# RGBoard.net
KiCad netlist of a schematic drawn in EAGLE
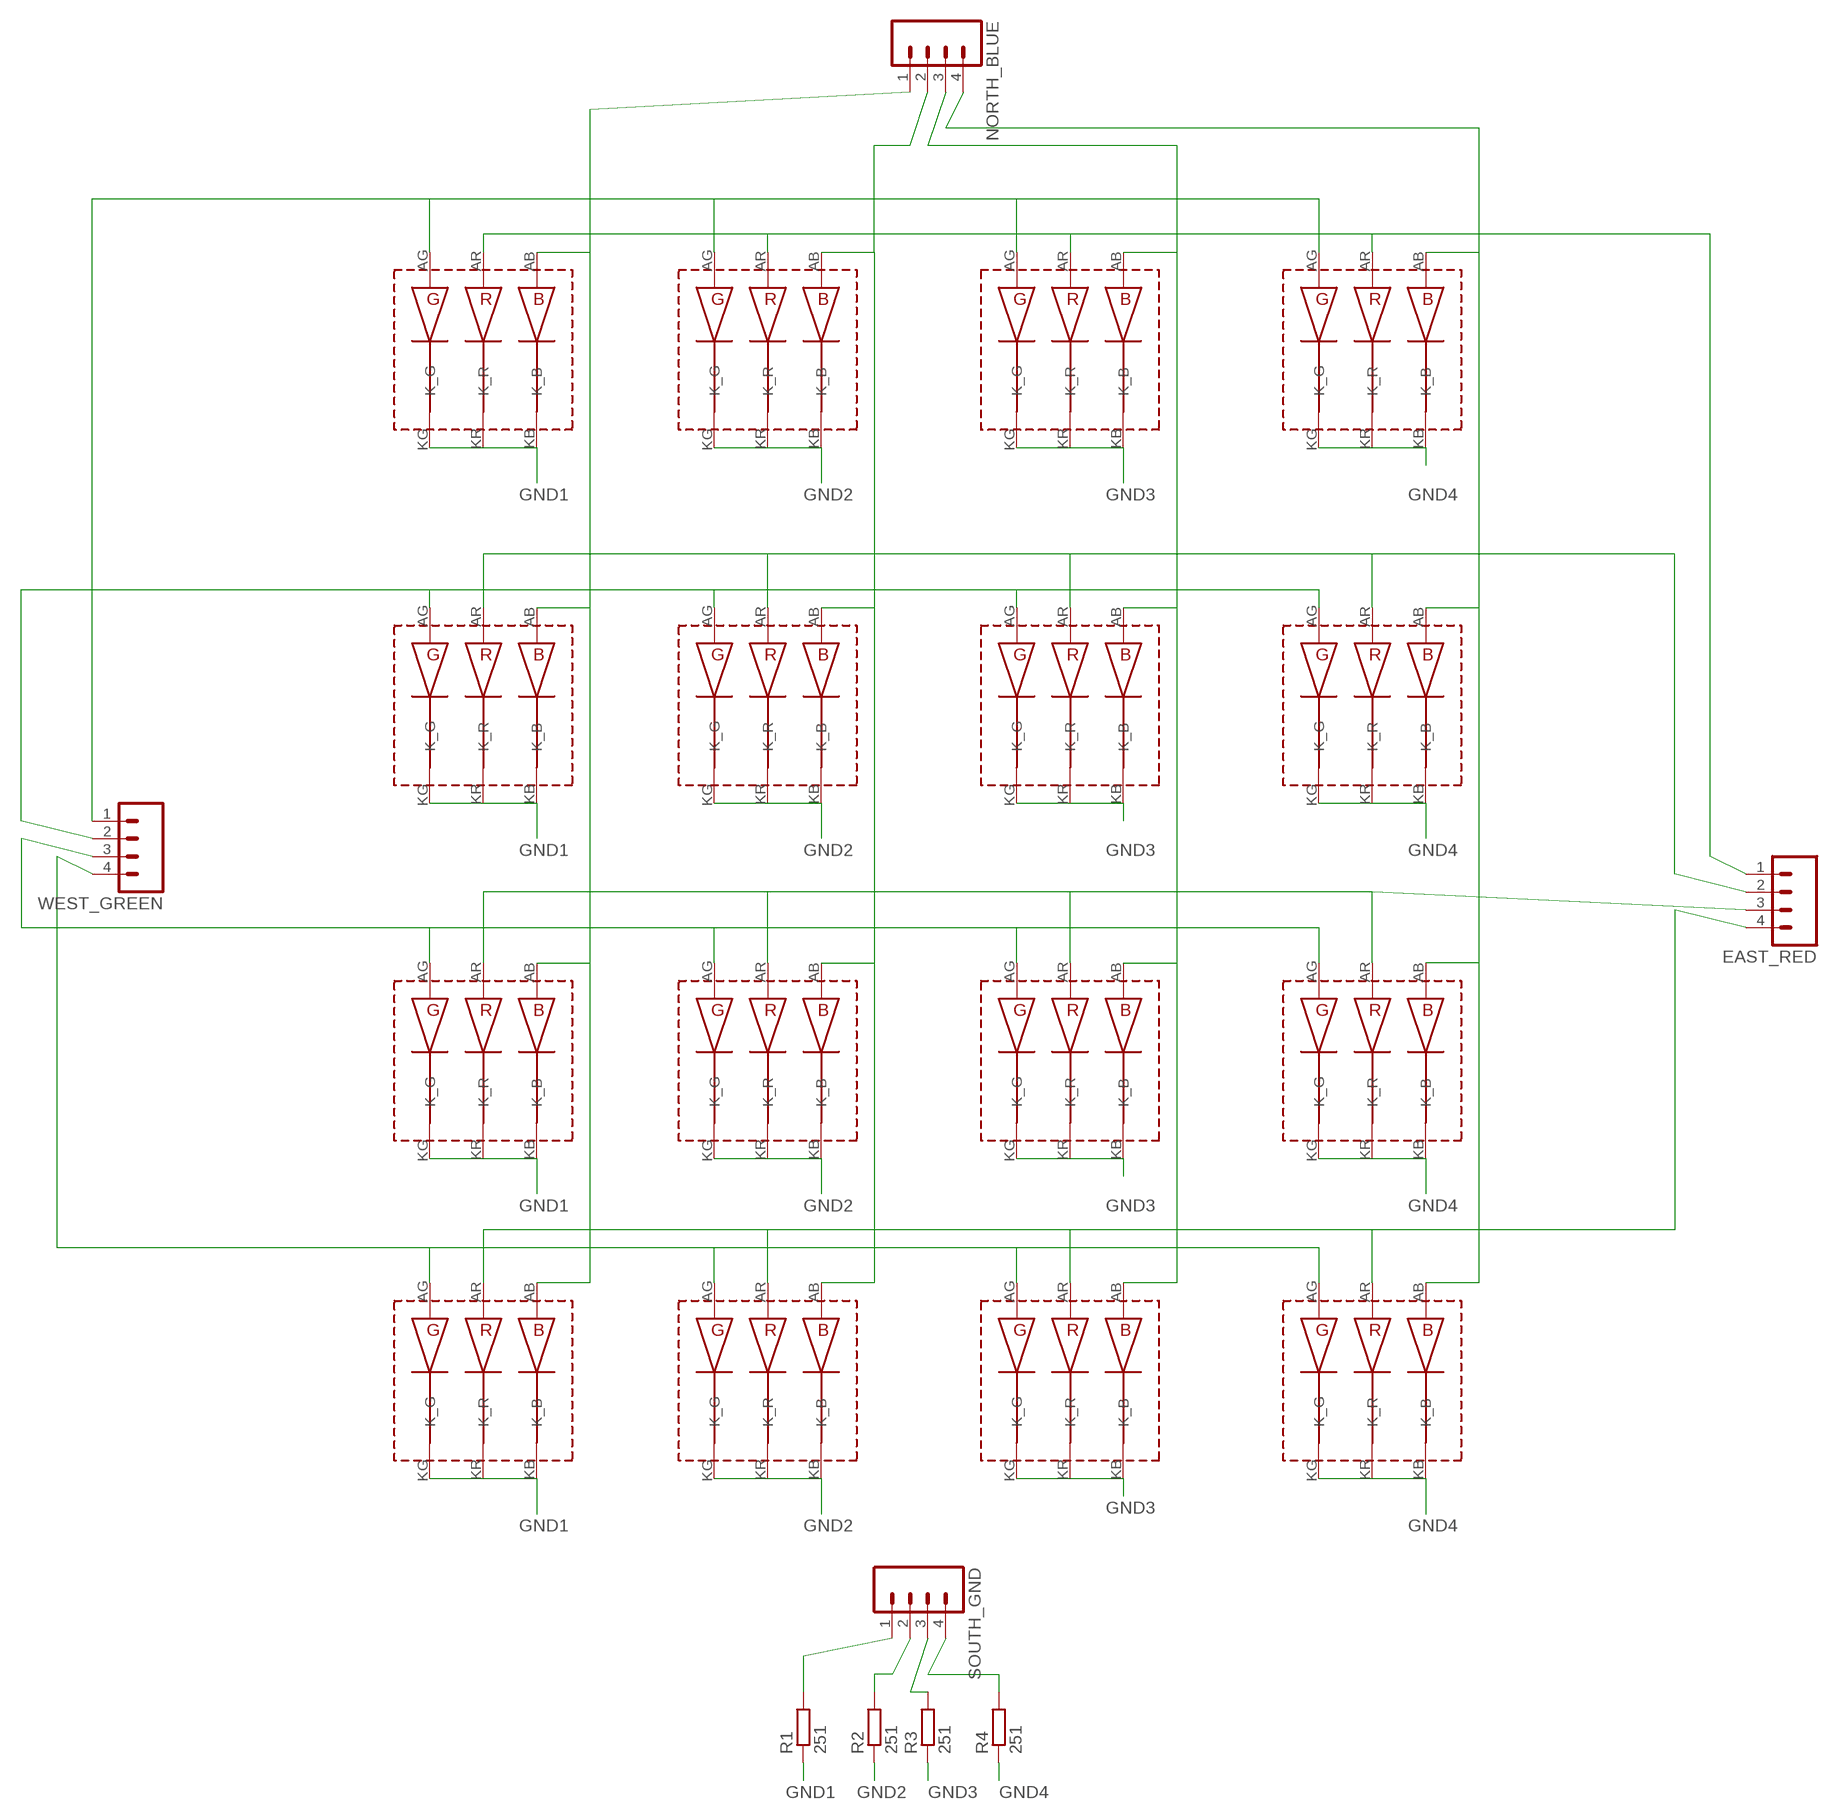
[diagram p0: schematic, sheet 1]

(export (version "E")
  (design (tool "Eeschema 10.0.6"))
  (components
    (comp (ref "A1")
      (value "RGB-SMT-SQUARE")
      (footprint "eagle-import:SMT-SQUARE6")
      (libsource (lib "eagle-import") (part "RGB-SMT-SQUARE"))
    )
    (comp (ref "A2")
      (value "RGB-SMT-SQUARE")
      (footprint "eagle-import:SMT-SQUARE6")
      (libsource (lib "eagle-import") (part "RGB-SMT-SQUARE"))
    )
    (comp (ref "A3")
      (value "RGB-SMT-SQUARE")
      (footprint "eagle-import:SMT-SQUARE6")
      (libsource (lib "eagle-import") (part "RGB-SMT-SQUARE"))
    )
    (comp (ref "A4")
      (value "RGB-SMT-SQUARE")
      (footprint "eagle-import:SMT-SQUARE6")
      (libsource (lib "eagle-import") (part "RGB-SMT-SQUARE"))
    )
    (comp (ref "B1")
      (value "RGB-SMT-SQUARE")
      (footprint "eagle-import:SMT-SQUARE6")
      (libsource (lib "eagle-import") (part "RGB-SMT-SQUARE"))
    )
    (comp (ref "B2")
      (value "RGB-SMT-SQUARE")
      (footprint "eagle-import:SMT-SQUARE6")
      (libsource (lib "eagle-import") (part "RGB-SMT-SQUARE"))
    )
    (comp (ref "B3")
      (value "RGB-SMT-SQUARE")
      (footprint "eagle-import:SMT-SQUARE6")
      (libsource (lib "eagle-import") (part "RGB-SMT-SQUARE"))
    )
    (comp (ref "B4")
      (value "RGB-SMT-SQUARE")
      (footprint "eagle-import:SMT-SQUARE6")
      (libsource (lib "eagle-import") (part "RGB-SMT-SQUARE"))
    )
    (comp (ref "C1")
      (value "RGB-SMT-SQUARE")
      (footprint "eagle-import:SMT-SQUARE6")
      (libsource (lib "eagle-import") (part "RGB-SMT-SQUARE"))
    )
    (comp (ref "C2")
      (value "RGB-SMT-SQUARE")
      (footprint "eagle-import:SMT-SQUARE6")
      (libsource (lib "eagle-import") (part "RGB-SMT-SQUARE"))
    )
    (comp (ref "C3")
      (value "RGB-SMT-SQUARE")
      (footprint "eagle-import:SMT-SQUARE6")
      (libsource (lib "eagle-import") (part "RGB-SMT-SQUARE"))
    )
    (comp (ref "C4")
      (value "RGB-SMT-SQUARE")
      (footprint "eagle-import:SMT-SQUARE6")
      (libsource (lib "eagle-import") (part "RGB-SMT-SQUARE"))
    )
    (comp (ref "D1")
      (value "RGB-SMT-SQUARE")
      (footprint "eagle-import:SMT-SQUARE6")
      (libsource (lib "eagle-import") (part "RGB-SMT-SQUARE"))
    )
    (comp (ref "D2")
      (value "RGB-SMT-SQUARE")
      (footprint "eagle-import:SMT-SQUARE6")
      (libsource (lib "eagle-import") (part "RGB-SMT-SQUARE"))
    )
    (comp (ref "D3")
      (value "RGB-SMT-SQUARE")
      (footprint "eagle-import:SMT-SQUARE6")
      (libsource (lib "eagle-import") (part "RGB-SMT-SQUARE"))
    )
    (comp (ref "D4")
      (value "RGB-SMT-SQUARE")
      (footprint "eagle-import:SMT-SQUARE6")
      (libsource (lib "eagle-import") (part "RGB-SMT-SQUARE"))
    )
    (comp (ref "EAST_RED")
      (value "M04PTH")
      (footprint "eagle-import:1X04")
      (libsource (lib "eagle-import") (part "M04PTH"))
    )
    (comp (ref "NORTH_BLUE")
      (value "M04PTH")
      (footprint "eagle-import:1X04")
      (libsource (lib "eagle-import") (part "M04PTH"))
    )
    (comp (ref "R1")
      (value "251")
      (footprint "eagle-import:0204_7")
      (libsource (lib "eagle-import") (part "R-EU_0204/7"))
    )
    (comp (ref "R2")
      (value "251")
      (footprint "eagle-import:0204_7")
      (libsource (lib "eagle-import") (part "R-EU_0204/7"))
    )
    (comp (ref "R3")
      (value "251")
      (footprint "eagle-import:0204_7")
      (libsource (lib "eagle-import") (part "R-EU_0204/7"))
    )
    (comp (ref "R4")
      (value "251")
      (footprint "eagle-import:0204_7")
      (libsource (lib "eagle-import") (part "R-EU_0204/7"))
    )
    (comp (ref "SOUTH_GND")
      (value "M04PTH")
      (footprint "eagle-import:1X04")
      (libsource (lib "eagle-import") (part "M04PTH"))
    )
    (comp (ref "WEST_GREEN")
      (value "M04PTH")
      (footprint "eagle-import:1X04")
      (libsource (lib "eagle-import") (part "M04PTH"))
    )
  )
  (nets
    (net (code "1") (name "/GND1") (class "Default")
      (node (ref "A1") (pin "KB") (pinfunction "K_B_KB") (pintype "bidirectional"))
      (node (ref "A1") (pin "KG") (pinfunction "K_G_KG") (pintype "bidirectional"))
      (node (ref "A1") (pin "KR") (pinfunction "K_R_KR") (pintype "bidirectional"))
      (node (ref "B1") (pin "KB") (pinfunction "K_B_KB") (pintype "bidirectional"))
      (node (ref "B1") (pin "KG") (pinfunction "K_G_KG") (pintype "bidirectional"))
      (node (ref "B1") (pin "KR") (pinfunction "K_R_KR") (pintype "bidirectional"))
      (node (ref "C1") (pin "KB") (pinfunction "K_B_KB") (pintype "bidirectional"))
      (node (ref "C1") (pin "KG") (pinfunction "K_G_KG") (pintype "bidirectional"))
      (node (ref "C1") (pin "KR") (pinfunction "K_R_KR") (pintype "bidirectional"))
      (node (ref "D1") (pin "KB") (pinfunction "K_B_KB") (pintype "bidirectional"))
      (node (ref "D1") (pin "KG") (pinfunction "K_G_KG") (pintype "bidirectional"))
      (node (ref "D1") (pin "KR") (pinfunction "K_R_KR") (pintype "bidirectional"))
      (node (ref "R1") (pin "1") (pinfunction "1_1") (pintype "passive"))
    )
    (net (code "2") (name "/GND2") (class "Default")
      (node (ref "A2") (pin "KB") (pinfunction "K_B_KB") (pintype "bidirectional"))
      (node (ref "A2") (pin "KG") (pinfunction "K_G_KG") (pintype "bidirectional"))
      (node (ref "A2") (pin "KR") (pinfunction "K_R_KR") (pintype "bidirectional"))
      (node (ref "B2") (pin "KB") (pinfunction "K_B_KB") (pintype "bidirectional"))
      (node (ref "B2") (pin "KG") (pinfunction "K_G_KG") (pintype "bidirectional"))
      (node (ref "B2") (pin "KR") (pinfunction "K_R_KR") (pintype "bidirectional"))
      (node (ref "C2") (pin "KB") (pinfunction "K_B_KB") (pintype "bidirectional"))
      (node (ref "C2") (pin "KG") (pinfunction "K_G_KG") (pintype "bidirectional"))
      (node (ref "C2") (pin "KR") (pinfunction "K_R_KR") (pintype "bidirectional"))
      (node (ref "D2") (pin "KB") (pinfunction "K_B_KB") (pintype "bidirectional"))
      (node (ref "D2") (pin "KG") (pinfunction "K_G_KG") (pintype "bidirectional"))
      (node (ref "D2") (pin "KR") (pinfunction "K_R_KR") (pintype "bidirectional"))
      (node (ref "R2") (pin "1") (pinfunction "1_1") (pintype "passive"))
    )
    (net (code "3") (name "/GND3") (class "Default")
      (node (ref "A3") (pin "KB") (pinfunction "K_B_KB") (pintype "bidirectional"))
      (node (ref "A3") (pin "KG") (pinfunction "K_G_KG") (pintype "bidirectional"))
      (node (ref "A3") (pin "KR") (pinfunction "K_R_KR") (pintype "bidirectional"))
      (node (ref "B3") (pin "KB") (pinfunction "K_B_KB") (pintype "bidirectional"))
      (node (ref "B3") (pin "KG") (pinfunction "K_G_KG") (pintype "bidirectional"))
      (node (ref "B3") (pin "KR") (pinfunction "K_R_KR") (pintype "bidirectional"))
      (node (ref "C3") (pin "KB") (pinfunction "K_B_KB") (pintype "bidirectional"))
      (node (ref "C3") (pin "KG") (pinfunction "K_G_KG") (pintype "bidirectional"))
      (node (ref "C3") (pin "KR") (pinfunction "K_R_KR") (pintype "bidirectional"))
      (node (ref "D3") (pin "KB") (pinfunction "K_B_KB") (pintype "bidirectional"))
      (node (ref "D3") (pin "KG") (pinfunction "K_G_KG") (pintype "bidirectional"))
      (node (ref "D3") (pin "KR") (pinfunction "K_R_KR") (pintype "bidirectional"))
      (node (ref "R3") (pin "1") (pinfunction "1_1") (pintype "passive"))
    )
    (net (code "4") (name "/GND4") (class "Default")
      (node (ref "A4") (pin "KB") (pinfunction "K_B_KB") (pintype "bidirectional"))
      (node (ref "A4") (pin "KG") (pinfunction "K_G_KG") (pintype "bidirectional"))
      (node (ref "A4") (pin "KR") (pinfunction "K_R_KR") (pintype "bidirectional"))
      (node (ref "B4") (pin "KB") (pinfunction "K_B_KB") (pintype "bidirectional"))
      (node (ref "B4") (pin "KG") (pinfunction "K_G_KG") (pintype "bidirectional"))
      (node (ref "B4") (pin "KR") (pinfunction "K_R_KR") (pintype "bidirectional"))
      (node (ref "C4") (pin "KB") (pinfunction "K_B_KB") (pintype "bidirectional"))
      (node (ref "C4") (pin "KG") (pinfunction "K_G_KG") (pintype "bidirectional"))
      (node (ref "C4") (pin "KR") (pinfunction "K_R_KR") (pintype "bidirectional"))
      (node (ref "D4") (pin "KB") (pinfunction "K_B_KB") (pintype "bidirectional"))
      (node (ref "D4") (pin "KG") (pinfunction "K_G_KG") (pintype "bidirectional"))
      (node (ref "D4") (pin "KR") (pinfunction "K_R_KR") (pintype "bidirectional"))
      (node (ref "R4") (pin "1") (pinfunction "1_1") (pintype "passive"))
    )
    (net (code "5") (name "Net-(A1-ANODE_B)") (class "Default")
      (node (ref "A1") (pin "AB") (pinfunction "ANODE_B_AB") (pintype "bidirectional"))
      (node (ref "B1") (pin "AB") (pinfunction "ANODE_B_AB") (pintype "bidirectional"))
      (node (ref "C1") (pin "AB") (pinfunction "ANODE_B_AB") (pintype "bidirectional"))
      (node (ref "D1") (pin "AB") (pinfunction "ANODE_B_AB") (pintype "bidirectional"))
      (node (ref "NORTH_BLUE") (pin "1") (pinfunction "1_1") (pintype "passive"))
    )
    (net (code "6") (name "Net-(A1-ANODE_G)") (class "Default")
      (node (ref "A1") (pin "AG") (pinfunction "ANODE_G_AG") (pintype "bidirectional"))
      (node (ref "A2") (pin "AG") (pinfunction "ANODE_G_AG") (pintype "bidirectional"))
      (node (ref "A3") (pin "AG") (pinfunction "ANODE_G_AG") (pintype "bidirectional"))
      (node (ref "A4") (pin "AG") (pinfunction "ANODE_G_AG") (pintype "bidirectional"))
      (node (ref "WEST_GREEN") (pin "1") (pinfunction "1_1") (pintype "passive"))
    )
    (net (code "7") (name "Net-(A1-ANODE_R)") (class "Default")
      (node (ref "A1") (pin "AR") (pinfunction "ANODE_R_AR") (pintype "bidirectional"))
      (node (ref "A2") (pin "AR") (pinfunction "ANODE_R_AR") (pintype "bidirectional"))
      (node (ref "A3") (pin "AR") (pinfunction "ANODE_R_AR") (pintype "bidirectional"))
      (node (ref "A4") (pin "AR") (pinfunction "ANODE_R_AR") (pintype "bidirectional"))
      (node (ref "EAST_RED") (pin "1") (pinfunction "1_1") (pintype "passive"))
    )
    (net (code "8") (name "Net-(A2-ANODE_B)") (class "Default")
      (node (ref "A2") (pin "AB") (pinfunction "ANODE_B_AB") (pintype "bidirectional"))
      (node (ref "B2") (pin "AB") (pinfunction "ANODE_B_AB") (pintype "bidirectional"))
      (node (ref "C2") (pin "AB") (pinfunction "ANODE_B_AB") (pintype "bidirectional"))
      (node (ref "D2") (pin "AB") (pinfunction "ANODE_B_AB") (pintype "bidirectional"))
      (node (ref "NORTH_BLUE") (pin "2") (pinfunction "2_2") (pintype "passive"))
    )
    (net (code "9") (name "Net-(A3-ANODE_B)") (class "Default")
      (node (ref "A3") (pin "AB") (pinfunction "ANODE_B_AB") (pintype "bidirectional"))
      (node (ref "B3") (pin "AB") (pinfunction "ANODE_B_AB") (pintype "bidirectional"))
      (node (ref "C3") (pin "AB") (pinfunction "ANODE_B_AB") (pintype "bidirectional"))
      (node (ref "D3") (pin "AB") (pinfunction "ANODE_B_AB") (pintype "bidirectional"))
      (node (ref "NORTH_BLUE") (pin "3") (pinfunction "3_3") (pintype "passive"))
    )
    (net (code "10") (name "Net-(A4-ANODE_B)") (class "Default")
      (node (ref "A4") (pin "AB") (pinfunction "ANODE_B_AB") (pintype "bidirectional"))
      (node (ref "B4") (pin "AB") (pinfunction "ANODE_B_AB") (pintype "bidirectional"))
      (node (ref "C4") (pin "AB") (pinfunction "ANODE_B_AB") (pintype "bidirectional"))
      (node (ref "D4") (pin "AB") (pinfunction "ANODE_B_AB") (pintype "bidirectional"))
      (node (ref "NORTH_BLUE") (pin "4") (pinfunction "4_4") (pintype "passive"))
    )
    (net (code "11") (name "Net-(B1-ANODE_G)") (class "Default")
      (node (ref "B1") (pin "AG") (pinfunction "ANODE_G_AG") (pintype "bidirectional"))
      (node (ref "B2") (pin "AG") (pinfunction "ANODE_G_AG") (pintype "bidirectional"))
      (node (ref "B3") (pin "AG") (pinfunction "ANODE_G_AG") (pintype "bidirectional"))
      (node (ref "B4") (pin "AG") (pinfunction "ANODE_G_AG") (pintype "bidirectional"))
      (node (ref "WEST_GREEN") (pin "2") (pinfunction "2_2") (pintype "passive"))
    )
    (net (code "12") (name "Net-(B1-ANODE_R)") (class "Default")
      (node (ref "B1") (pin "AR") (pinfunction "ANODE_R_AR") (pintype "bidirectional"))
      (node (ref "B2") (pin "AR") (pinfunction "ANODE_R_AR") (pintype "bidirectional"))
      (node (ref "B3") (pin "AR") (pinfunction "ANODE_R_AR") (pintype "bidirectional"))
      (node (ref "B4") (pin "AR") (pinfunction "ANODE_R_AR") (pintype "bidirectional"))
      (node (ref "EAST_RED") (pin "2") (pinfunction "2_2") (pintype "passive"))
    )
    (net (code "13") (name "Net-(C1-ANODE_G)") (class "Default")
      (node (ref "C1") (pin "AG") (pinfunction "ANODE_G_AG") (pintype "bidirectional"))
      (node (ref "C2") (pin "AG") (pinfunction "ANODE_G_AG") (pintype "bidirectional"))
      (node (ref "C3") (pin "AG") (pinfunction "ANODE_G_AG") (pintype "bidirectional"))
      (node (ref "C4") (pin "AG") (pinfunction "ANODE_G_AG") (pintype "bidirectional"))
      (node (ref "WEST_GREEN") (pin "3") (pinfunction "3_3") (pintype "passive"))
    )
    (net (code "14") (name "Net-(C1-ANODE_R)") (class "Default")
      (node (ref "C1") (pin "AR") (pinfunction "ANODE_R_AR") (pintype "bidirectional"))
      (node (ref "C2") (pin "AR") (pinfunction "ANODE_R_AR") (pintype "bidirectional"))
      (node (ref "C3") (pin "AR") (pinfunction "ANODE_R_AR") (pintype "bidirectional"))
      (node (ref "C4") (pin "AR") (pinfunction "ANODE_R_AR") (pintype "bidirectional"))
      (node (ref "EAST_RED") (pin "3") (pinfunction "3_3") (pintype "passive"))
    )
    (net (code "15") (name "Net-(D1-ANODE_G)") (class "Default")
      (node (ref "D1") (pin "AG") (pinfunction "ANODE_G_AG") (pintype "bidirectional"))
      (node (ref "D2") (pin "AG") (pinfunction "ANODE_G_AG") (pintype "bidirectional"))
      (node (ref "D3") (pin "AG") (pinfunction "ANODE_G_AG") (pintype "bidirectional"))
      (node (ref "D4") (pin "AG") (pinfunction "ANODE_G_AG") (pintype "bidirectional"))
      (node (ref "WEST_GREEN") (pin "4") (pinfunction "4_4") (pintype "passive"))
    )
    (net (code "16") (name "Net-(D1-ANODE_R)") (class "Default")
      (node (ref "D1") (pin "AR") (pinfunction "ANODE_R_AR") (pintype "bidirectional"))
      (node (ref "D2") (pin "AR") (pinfunction "ANODE_R_AR") (pintype "bidirectional"))
      (node (ref "D3") (pin "AR") (pinfunction "ANODE_R_AR") (pintype "bidirectional"))
      (node (ref "D4") (pin "AR") (pinfunction "ANODE_R_AR") (pintype "bidirectional"))
      (node (ref "EAST_RED") (pin "4") (pinfunction "4_4") (pintype "passive"))
    )
    (net (code "17") (name "Net-(R1-Pad2)") (class "Default")
      (node (ref "R1") (pin "2") (pinfunction "2_2") (pintype "passive"))
      (node (ref "SOUTH_GND") (pin "1") (pinfunction "1_1") (pintype "passive"))
    )
    (net (code "18") (name "Net-(R2-Pad2)") (class "Default")
      (node (ref "R2") (pin "2") (pinfunction "2_2") (pintype "passive"))
      (node (ref "SOUTH_GND") (pin "2") (pinfunction "2_2") (pintype "passive"))
    )
    (net (code "19") (name "Net-(R3-Pad2)") (class "Default")
      (node (ref "R3") (pin "2") (pinfunction "2_2") (pintype "passive"))
      (node (ref "SOUTH_GND") (pin "3") (pinfunction "3_3") (pintype "passive"))
    )
    (net (code "20") (name "Net-(R4-Pad2)") (class "Default")
      (node (ref "R4") (pin "2") (pinfunction "2_2") (pintype "passive"))
      (node (ref "SOUTH_GND") (pin "4") (pinfunction "4_4") (pintype "passive"))
    )
  )
)
